# REMOTE.net
KiCad netlist of a schematic drawn in EAGLE
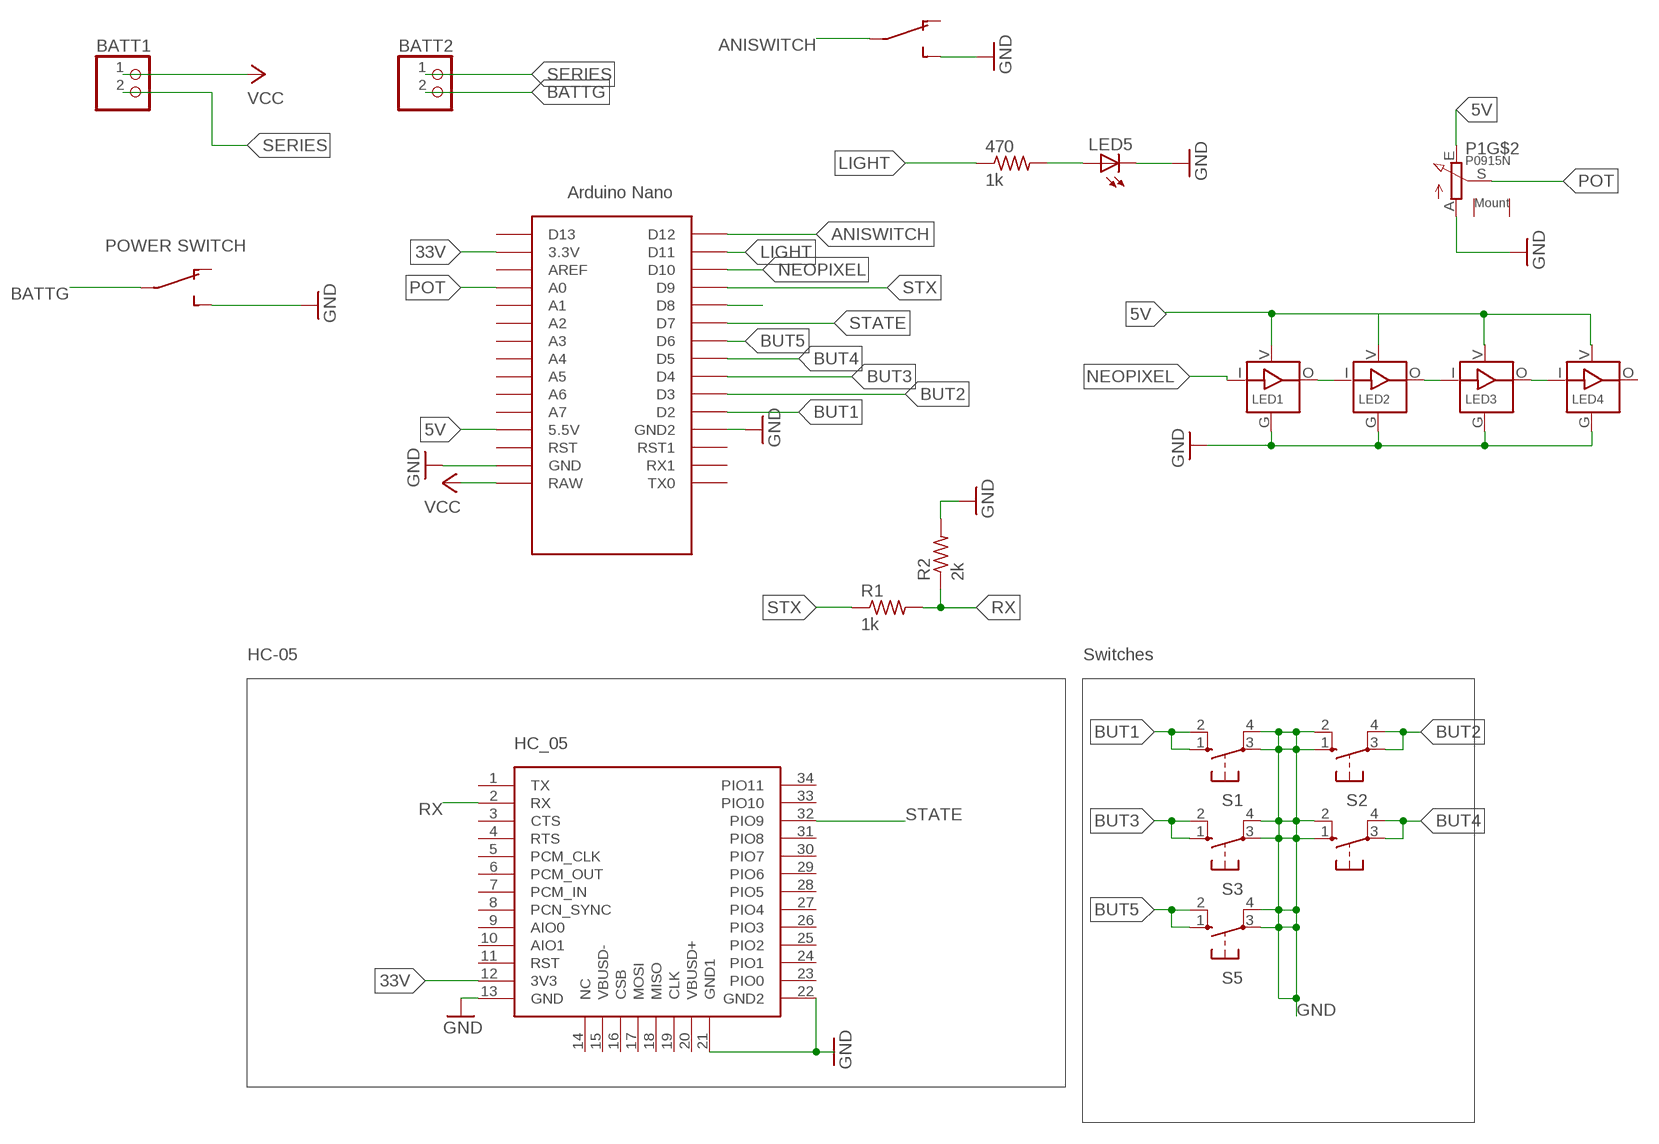
[diagram p0: schematic, sheet 1]

(export (version "E")
  (design (tool "Eeschema 10.0.6"))
  (components
    (comp (ref "470")
      (value "1k")
      (footprint "eagle-import:R2010")
      (libsource (lib "eagle-import") (part "R-US_R2010"))
    )
    (comp (ref "BATT1")
      (value "PINHD-1X2")
      (footprint "eagle-import:1X02")
      (libsource (lib "eagle-import") (part "PINHD-1X2"))
    )
    (comp (ref "BATT2")
      (value "PINHD-1X2")
      (footprint "eagle-import:1X02")
      (libsource (lib "eagle-import") (part "PINHD-1X2"))
    )
    (comp (ref "LED1")
      (value "SK6812_3535")
      (footprint "eagle-import:LED3535")
      (libsource (lib "eagle-import") (part "SK6812_3535"))
    )
    (comp (ref "LED2")
      (value "SK6812_3535")
      (footprint "eagle-import:LED3535")
      (libsource (lib "eagle-import") (part "SK6812_3535"))
    )
    (comp (ref "LED3")
      (value "SK6812_3535")
      (footprint "eagle-import:LED3535")
      (libsource (lib "eagle-import") (part "SK6812_3535"))
    )
    (comp (ref "LED4")
      (value "SK6812_3535")
      (footprint "eagle-import:LED3535")
      (libsource (lib "eagle-import") (part "SK6812_3535"))
    )
    (comp (ref "LED5")
      (value "LED3MM")
      (footprint "eagle-import:LED3MM")
      (libsource (lib "eagle-import") (part "LED3MM"))
    )
    (comp (ref "P1")
      (value "P0915N")
      (footprint "eagle-import:P0915N")
      (libsource (lib "eagle-import") (part "P0915N"))
    )
    (comp (ref "POWER")
      (value "DPDT_JS202011CQN")
      (footprint "eagle-import:DPDT_JS202011CQN")
      (libsource (lib "eagle-import") (part "DPDT_JS202011CQN"))
    )
    (comp (ref "POWER1")
      (value "DPDT_JS202011CQN")
      (footprint "eagle-import:DPDT_JS202011CQN")
      (libsource (lib "eagle-import") (part "DPDT_JS202011CQN"))
    )
    (comp (ref "R1")
      (value "1k")
      (footprint "eagle-import:R2010")
      (libsource (lib "eagle-import") (part "R-US_R2010"))
    )
    (comp (ref "R2")
      (value "2k")
      (footprint "eagle-import:R2010")
      (libsource (lib "eagle-import") (part "R-US_R2010"))
    )
    (comp (ref "S1")
      (value "10-XX")
      (footprint "eagle-import:B3F-10XX")
      (fields (field (name "MPN") "B3F-1000"))
      (libsource (lib "eagle-import") (part "10-XX"))
    )
    (comp (ref "S2")
      (value "10-XX")
      (footprint "eagle-import:B3F-10XX")
      (fields (field (name "MPN") "B3F-1000"))
      (libsource (lib "eagle-import") (part "10-XX"))
    )
    (comp (ref "S3")
      (value "10-XX")
      (footprint "eagle-import:B3F-10XX")
      (fields (field (name "MPN") "B3F-1000"))
      (libsource (lib "eagle-import") (part "10-XX"))
    )
    (comp (ref "S4")
      (value "10-XX")
      (footprint "eagle-import:B3F-10XX")
      (fields (field (name "MPN") "B3F-1000"))
      (libsource (lib "eagle-import") (part "10-XX"))
    )
    (comp (ref "S5")
      (value "10-XX")
      (footprint "eagle-import:B3F-10XX")
      (fields (field (name "MPN") "B3F-1000"))
      (libsource (lib "eagle-import") (part "10-XX"))
    )
    (comp (ref "U$1")
      (value "NANO")
      (footprint "eagle-import:NANO")
      (libsource (lib "eagle-import") (part "NANO"))
    )
    (comp (ref "U2")
      (value "HC_05")
      (footprint "eagle-import:BLUETOOTH_SMD")
      (libsource (lib "eagle-import") (part "HC_05"))
    )
  )
  (nets
    (net (code "1") (name "5V") (class "Default")
      (node (ref "LED1") (pin "V") (pinfunction "VDD_V") (pintype "power_in"))
      (node (ref "LED2") (pin "V") (pinfunction "VDD_V") (pintype "power_in"))
      (node (ref "LED3") (pin "V") (pinfunction "VDD_V") (pintype "power_in"))
      (node (ref "LED4") (pin "V") (pinfunction "VDD_V") (pintype "power_in"))
      (node (ref "P1") (pin "E") (pinfunction "E_E") (pintype "passive"))
      (node (ref "U$1") (pin "5V") (pinfunction "5.5V_5V") (pintype "bidirectional"))
    )
    (net (code "2") (name "33V") (class "Default")
      (node (ref "U$1") (pin "3.3V") (pinfunction "3.3V_3.3V") (pintype "bidirectional"))
      (node (ref "U2") (pin "12") (pinfunction "3V3_12") (pintype "bidirectional"))
    )
    (net (code "3") (name "ANISWITCH") (class "Default")
      (node (ref "POWER1") (pin "2") (pinfunction "P_2") (pintype "passive"))
      (node (ref "U$1") (pin "D12") (pinfunction "D12_D12") (pintype "bidirectional"))
    )
    (net (code "4") (name "BATTG") (class "Default")
      (node (ref "BATT2") (pin "2") (pinfunction "2_2") (pintype "passive"))
      (node (ref "POWER") (pin "2") (pinfunction "P_2") (pintype "passive"))
    )
    (net (code "5") (name "BUT1") (class "Default")
      (node (ref "S1") (pin "1") (pinfunction "S_1") (pintype "passive"))
      (node (ref "S1") (pin "2") (pinfunction "S1_2") (pintype "passive"))
      (node (ref "U$1") (pin "D2") (pinfunction "D2_D2") (pintype "bidirectional"))
    )
    (net (code "6") (name "BUT2") (class "Default")
      (node (ref "S2") (pin "3") (pinfunction "P_3") (pintype "passive"))
      (node (ref "S2") (pin "4") (pinfunction "P1_4") (pintype "passive"))
      (node (ref "U$1") (pin "D3") (pinfunction "D3_D3") (pintype "bidirectional"))
    )
    (net (code "7") (name "BUT3") (class "Default")
      (node (ref "S3") (pin "1") (pinfunction "S_1") (pintype "passive"))
      (node (ref "S3") (pin "2") (pinfunction "S1_2") (pintype "passive"))
      (node (ref "U$1") (pin "D4") (pinfunction "D4_D4") (pintype "bidirectional"))
    )
    (net (code "8") (name "BUT4") (class "Default")
      (node (ref "S4") (pin "3") (pinfunction "P_3") (pintype "passive"))
      (node (ref "S4") (pin "4") (pinfunction "P1_4") (pintype "passive"))
      (node (ref "U$1") (pin "D5") (pinfunction "D5_D5") (pintype "bidirectional"))
    )
    (net (code "9") (name "BUT5") (class "Default")
      (node (ref "S5") (pin "1") (pinfunction "S_1") (pintype "passive"))
      (node (ref "S5") (pin "2") (pinfunction "S1_2") (pintype "passive"))
      (node (ref "U$1") (pin "D6") (pinfunction "D6_D6") (pintype "bidirectional"))
    )
    (net (code "10") (name "GND") (class "Default")
      (node (ref "LED1") (pin "G") (pinfunction "GND_G") (pintype "power_in"))
      (node (ref "LED2") (pin "G") (pinfunction "GND_G") (pintype "power_in"))
      (node (ref "LED3") (pin "G") (pinfunction "GND_G") (pintype "power_in"))
      (node (ref "LED4") (pin "G") (pinfunction "GND_G") (pintype "power_in"))
      (node (ref "LED5") (pin "K") (pinfunction "C_K") (pintype "passive"))
      (node (ref "P1") (pin "A") (pinfunction "A_A") (pintype "passive"))
      (node (ref "POWER") (pin "3") (pinfunction "O2_3") (pintype "passive"))
      (node (ref "POWER1") (pin "3") (pinfunction "O2_3") (pintype "passive"))
      (node (ref "R2") (pin "2") (pinfunction "2_2") (pintype "passive"))
      (node (ref "S1") (pin "3") (pinfunction "P_3") (pintype "passive"))
      (node (ref "S1") (pin "4") (pinfunction "P1_4") (pintype "passive"))
      (node (ref "S2") (pin "1") (pinfunction "S_1") (pintype "passive"))
      (node (ref "S2") (pin "2") (pinfunction "S1_2") (pintype "passive"))
      (node (ref "S3") (pin "3") (pinfunction "P_3") (pintype "passive"))
      (node (ref "S3") (pin "4") (pinfunction "P1_4") (pintype "passive"))
      (node (ref "S4") (pin "1") (pinfunction "S_1") (pintype "passive"))
      (node (ref "S4") (pin "2") (pinfunction "S1_2") (pintype "passive"))
      (node (ref "S5") (pin "3") (pinfunction "P_3") (pintype "passive"))
      (node (ref "S5") (pin "4") (pinfunction "P1_4") (pintype "passive"))
      (node (ref "U$1") (pin "GND") (pinfunction "GND_GND") (pintype "bidirectional"))
      (node (ref "U$1") (pin "GND1") (pinfunction "GND2_GND1") (pintype "bidirectional"))
      (node (ref "U2") (pin "13") (pinfunction "GND_13") (pintype "bidirectional"))
      (node (ref "U2") (pin "21") (pinfunction "GND1_21") (pintype "bidirectional"))
      (node (ref "U2") (pin "22") (pinfunction "GND2_22") (pintype "bidirectional"))
    )
    (net (code "11") (name "LIGHT") (class "Default")
      (node (ref "470") (pin "1") (pinfunction "1_1") (pintype "passive"))
      (node (ref "U$1") (pin "D11") (pinfunction "D11_D11") (pintype "bidirectional"))
    )
    (net (code "12") (name "NEOPIXEL") (class "Default")
      (node (ref "LED1") (pin "I") (pinfunction "DI_I") (pintype "input"))
      (node (ref "U$1") (pin "D10") (pinfunction "D10_D10") (pintype "bidirectional"))
    )
    (net (code "13") (name "Net-(470-Pad2)") (class "Default")
      (node (ref "470") (pin "2") (pinfunction "2_2") (pintype "passive"))
      (node (ref "LED5") (pin "A") (pinfunction "A_A") (pintype "passive"))
    )
    (net (code "14") (name "Net-(LED1-DO)") (class "Default")
      (node (ref "LED1") (pin "O") (pinfunction "DO_O") (pintype "output"))
      (node (ref "LED2") (pin "I") (pinfunction "DI_I") (pintype "input"))
    )
    (net (code "15") (name "Net-(LED2-DO)") (class "Default")
      (node (ref "LED2") (pin "O") (pinfunction "DO_O") (pintype "output"))
      (node (ref "LED3") (pin "I") (pinfunction "DI_I") (pintype "input"))
    )
    (net (code "16") (name "Net-(LED3-DO)") (class "Default")
      (node (ref "LED3") (pin "O") (pinfunction "DO_O") (pintype "output"))
      (node (ref "LED4") (pin "I") (pinfunction "DI_I") (pintype "input"))
    )
    (net (code "17") (name "POT") (class "Default")
      (node (ref "P1") (pin "S") (pinfunction "S_S") (pintype "passive"))
      (node (ref "U$1") (pin "A0") (pinfunction "A0_A0") (pintype "bidirectional"))
    )
    (net (code "18") (name "RX") (class "Default")
      (node (ref "R1") (pin "2") (pinfunction "2_2") (pintype "passive"))
      (node (ref "R2") (pin "1") (pinfunction "1_1") (pintype "passive"))
      (node (ref "U2") (pin "2") (pinfunction "RX_2") (pintype "bidirectional"))
    )
    (net (code "19") (name "SERIES") (class "Default")
      (node (ref "BATT1") (pin "2") (pinfunction "2_2") (pintype "passive"))
      (node (ref "BATT2") (pin "1") (pinfunction "1_1") (pintype "passive"))
    )
    (net (code "20") (name "STATE") (class "Default")
      (node (ref "U$1") (pin "D7") (pinfunction "D7_D7") (pintype "bidirectional"))
      (node (ref "U2") (pin "32") (pinfunction "PIO9_32") (pintype "bidirectional"))
    )
    (net (code "21") (name "STX") (class "Default")
      (node (ref "R1") (pin "1") (pinfunction "1_1") (pintype "passive"))
      (node (ref "U$1") (pin "D9") (pinfunction "D9_D9") (pintype "bidirectional"))
    )
    (net (code "22") (name "VCC") (class "Default")
      (node (ref "BATT1") (pin "1") (pinfunction "1_1") (pintype "passive"))
      (node (ref "U$1") (pin "RAW") (pinfunction "RAW_RAW") (pintype "bidirectional"))
    )
    (net (code "23") (name "unconnected-(LED4-DO-PadO)") (class "Default")
      (node (ref "LED4") (pin "O") (pinfunction "DO_O") (pintype "output"))
    )
    (net (code "24") (name "unconnected-(P1A-GND-PadGND@1)") (class "Default")
      (node (ref "P1") (pin "GND@1") (pinfunction "GND_GND@1") (pintype "passive"))
    )
    (net (code "25") (name "unconnected-(P1A-GND-PadGND@2)") (class "Default")
      (node (ref "P1") (pin "GND@2") (pinfunction "GND_GND@2") (pintype "passive"))
    )
    (net (code "26") (name "unconnected-(POWER1A-O1-Pad1)") (class "Default")
      (node (ref "POWER1") (pin "1") (pinfunction "O1_1") (pintype "passive"))
    )
    (net (code "27") (name "unconnected-(POWERA-O1-Pad1)") (class "Default")
      (node (ref "POWER") (pin "1") (pinfunction "O1_1") (pintype "passive"))
    )
    (net (code "28") (name "unconnected-(U$1-PadA1)") (class "Default")
      (node (ref "U$1") (pin "A1") (pinfunction "A1_A1") (pintype "bidirectional"))
    )
    (net (code "29") (name "unconnected-(U$1-PadA2)") (class "Default")
      (node (ref "U$1") (pin "A2") (pinfunction "A2_A2") (pintype "bidirectional"))
    )
    (net (code "30") (name "unconnected-(U$1-PadA3)") (class "Default")
      (node (ref "U$1") (pin "A3") (pinfunction "A3_A3") (pintype "bidirectional"))
    )
    (net (code "31") (name "unconnected-(U$1-PadA4)") (class "Default")
      (node (ref "U$1") (pin "A4") (pinfunction "A4_A4") (pintype "bidirectional"))
    )
    (net (code "32") (name "unconnected-(U$1-PadA5)") (class "Default")
      (node (ref "U$1") (pin "A5") (pinfunction "A5_A5") (pintype "bidirectional"))
    )
    (net (code "33") (name "unconnected-(U$1-PadA6)") (class "Default")
      (node (ref "U$1") (pin "A6") (pinfunction "A6_A6") (pintype "bidirectional"))
    )
    (net (code "34") (name "unconnected-(U$1-PadA7)") (class "Default")
      (node (ref "U$1") (pin "A7") (pinfunction "A7_A7") (pintype "bidirectional"))
    )
    (net (code "35") (name "unconnected-(U$1-PadAREF)") (class "Default")
      (node (ref "U$1") (pin "AREF") (pinfunction "AREF_AREF") (pintype "bidirectional"))
    )
    (net (code "36") (name "unconnected-(U$1-PadD8)") (class "Default")
      (node (ref "U$1") (pin "D8") (pinfunction "D8_D8") (pintype "bidirectional"))
    )
    (net (code "37") (name "unconnected-(U$1-PadD13)") (class "Default")
      (node (ref "U$1") (pin "D13") (pinfunction "D13_D13") (pintype "bidirectional"))
    )
    (net (code "38") (name "unconnected-(U$1-PadICSP1)") (class "Default")
      (node (ref "U$1") (pin "ICSP1") (pinfunction "ICSP1_ICSP1") (pintype "bidirectional"))
    )
    (net (code "39") (name "unconnected-(U$1-PadICSP2)") (class "Default")
      (node (ref "U$1") (pin "ICSP2") (pinfunction "ICSP2_ICSP2") (pintype "bidirectional"))
    )
    (net (code "40") (name "unconnected-(U$1-PadICSP3)") (class "Default")
      (node (ref "U$1") (pin "ICSP3") (pinfunction "ICSP3_ICSP3") (pintype "bidirectional"))
    )
    (net (code "41") (name "unconnected-(U$1-PadICSP4)") (class "Default")
      (node (ref "U$1") (pin "ICSP4") (pinfunction "ICSP4_ICSP4") (pintype "bidirectional"))
    )
    (net (code "42") (name "unconnected-(U$1-PadICSP5)") (class "Default")
      (node (ref "U$1") (pin "ICSP5") (pinfunction "ICSP5_ICSP5") (pintype "bidirectional"))
    )
    (net (code "43") (name "unconnected-(U$1-PadICSP6)") (class "Default")
      (node (ref "U$1") (pin "ICSP6") (pinfunction "ICSP6_ICSP6") (pintype "bidirectional"))
    )
    (net (code "44") (name "unconnected-(U$1-PadRST)") (class "Default")
      (node (ref "U$1") (pin "RST") (pinfunction "RST_RST") (pintype "bidirectional"))
    )
    (net (code "45") (name "unconnected-(U$1-PadRST1)") (class "Default")
      (node (ref "U$1") (pin "RST1") (pinfunction "RST1_RST1") (pintype "bidirectional"))
    )
    (net (code "46") (name "unconnected-(U$1-PadRX1)") (class "Default")
      (node (ref "U$1") (pin "RX1") (pinfunction "RX1_RX1") (pintype "bidirectional"))
    )
    (net (code "47") (name "unconnected-(U$1-PadTX0)") (class "Default")
      (node (ref "U$1") (pin "TX0") (pinfunction "TX0_TX0") (pintype "bidirectional"))
    )
    (net (code "48") (name "unconnected-(U2-AIO0-Pad9)") (class "Default")
      (node (ref "U2") (pin "9") (pinfunction "AIO0_9") (pintype "bidirectional"))
    )
    (net (code "49") (name "unconnected-(U2-AIO1-Pad10)") (class "Default")
      (node (ref "U2") (pin "10") (pinfunction "AIO1_10") (pintype "bidirectional"))
    )
    (net (code "50") (name "unconnected-(U2-CLK-Pad19)") (class "Default")
      (node (ref "U2") (pin "19") (pinfunction "CLK_19") (pintype "bidirectional"))
    )
    (net (code "51") (name "unconnected-(U2-CSB-Pad16)") (class "Default")
      (node (ref "U2") (pin "16") (pinfunction "CSB_16") (pintype "bidirectional"))
    )
    (net (code "52") (name "unconnected-(U2-CTS-Pad3)") (class "Default")
      (node (ref "U2") (pin "3") (pinfunction "CTS_3") (pintype "bidirectional"))
    )
    (net (code "53") (name "unconnected-(U2-MISO-Pad18)") (class "Default")
      (node (ref "U2") (pin "18") (pinfunction "MISO_18") (pintype "bidirectional"))
    )
    (net (code "54") (name "unconnected-(U2-MOSI-Pad17)") (class "Default")
      (node (ref "U2") (pin "17") (pinfunction "MOSI_17") (pintype "bidirectional"))
    )
    (net (code "55") (name "unconnected-(U2-NC-Pad14)") (class "Default")
      (node (ref "U2") (pin "14") (pinfunction "NC_14") (pintype "bidirectional"))
    )
    (net (code "56") (name "unconnected-(U2-PCM_CLK-Pad5)") (class "Default")
      (node (ref "U2") (pin "5") (pinfunction "PCM_CLK_5") (pintype "bidirectional"))
    )
    (net (code "57") (name "unconnected-(U2-PCM_IN-Pad7)") (class "Default")
      (node (ref "U2") (pin "7") (pinfunction "PCM_IN_7") (pintype "bidirectional"))
    )
    (net (code "58") (name "unconnected-(U2-PCM_OUT-Pad6)") (class "Default")
      (node (ref "U2") (pin "6") (pinfunction "PCM_OUT_6") (pintype "bidirectional"))
    )
    (net (code "59") (name "unconnected-(U2-PCN_SYNC-Pad8)") (class "Default")
      (node (ref "U2") (pin "8") (pinfunction "PCN_SYNC_8") (pintype "bidirectional"))
    )
    (net (code "60") (name "unconnected-(U2-PIO0-Pad23)") (class "Default")
      (node (ref "U2") (pin "23") (pinfunction "PIO0_23") (pintype "bidirectional"))
    )
    (net (code "61") (name "unconnected-(U2-PIO1-Pad24)") (class "Default")
      (node (ref "U2") (pin "24") (pinfunction "PIO1_24") (pintype "bidirectional"))
    )
    (net (code "62") (name "unconnected-(U2-PIO2-Pad25)") (class "Default")
      (node (ref "U2") (pin "25") (pinfunction "PIO2_25") (pintype "bidirectional"))
    )
    (net (code "63") (name "unconnected-(U2-PIO3-Pad26)") (class "Default")
      (node (ref "U2") (pin "26") (pinfunction "PIO3_26") (pintype "bidirectional"))
    )
    (net (code "64") (name "unconnected-(U2-PIO4-Pad27)") (class "Default")
      (node (ref "U2") (pin "27") (pinfunction "PIO4_27") (pintype "bidirectional"))
    )
    (net (code "65") (name "unconnected-(U2-PIO5-Pad28)") (class "Default")
      (node (ref "U2") (pin "28") (pinfunction "PIO5_28") (pintype "bidirectional"))
    )
    (net (code "66") (name "unconnected-(U2-PIO6-Pad29)") (class "Default")
      (node (ref "U2") (pin "29") (pinfunction "PIO6_29") (pintype "bidirectional"))
    )
    (net (code "67") (name "unconnected-(U2-PIO7-Pad30)") (class "Default")
      (node (ref "U2") (pin "30") (pinfunction "PIO7_30") (pintype "bidirectional"))
    )
    (net (code "68") (name "unconnected-(U2-PIO8-Pad31)") (class "Default")
      (node (ref "U2") (pin "31") (pinfunction "PIO8_31") (pintype "bidirectional"))
    )
    (net (code "69") (name "unconnected-(U2-PIO10-Pad33)") (class "Default")
      (node (ref "U2") (pin "33") (pinfunction "PIO10_33") (pintype "bidirectional"))
    )
    (net (code "70") (name "unconnected-(U2-PIO11-Pad34)") (class "Default")
      (node (ref "U2") (pin "34") (pinfunction "PIO11_34") (pintype "bidirectional"))
    )
    (net (code "71") (name "unconnected-(U2-RST-Pad11)") (class "Default")
      (node (ref "U2") (pin "11") (pinfunction "RST_11") (pintype "bidirectional"))
    )
    (net (code "72") (name "unconnected-(U2-RTS-Pad4)") (class "Default")
      (node (ref "U2") (pin "4") (pinfunction "RTS_4") (pintype "bidirectional"))
    )
    (net (code "73") (name "unconnected-(U2-TX-Pad1)") (class "Default")
      (node (ref "U2") (pin "1") (pinfunction "TX_1") (pintype "bidirectional"))
    )
    (net (code "74") (name "unconnected-(U2-VBUSD+-Pad20)") (class "Default")
      (node (ref "U2") (pin "20") (pinfunction "VBUSD+_20") (pintype "bidirectional"))
    )
    (net (code "75") (name "unconnected-(U2-VBUSD--Pad15)") (class "Default")
      (node (ref "U2") (pin "15") (pinfunction "VBUSD-_15") (pintype "bidirectional"))
    )
  )
)
